# breadboard_power_supply_smd.net
KiCad netlist of a schematic drawn in EAGLE
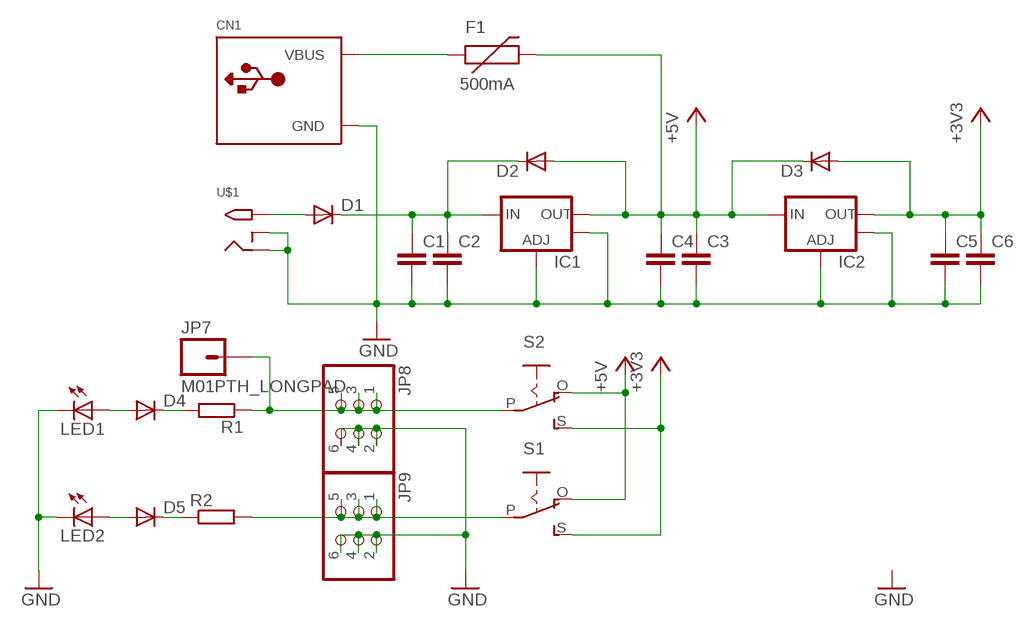
[diagram p0: schematic, sheet 1]

(export (version "E")
  (design (tool "Eeschema 10.0.6"))
  (components
    (comp (ref "C1")
      (value "C-EUC0805K")
      (footprint "eagle-import:C0805K")
      (libsource (lib "eagle-import") (part "C-EUC0805K"))
    )
    (comp (ref "C2")
      (value "C-EUC0805K")
      (footprint "eagle-import:C0805K")
      (libsource (lib "eagle-import") (part "C-EUC0805K"))
    )
    (comp (ref "C3")
      (value "C-EUC0805K")
      (footprint "eagle-import:C0805K")
      (libsource (lib "eagle-import") (part "C-EUC0805K"))
    )
    (comp (ref "C4")
      (value "C-EUC0805K")
      (footprint "eagle-import:C0805K")
      (libsource (lib "eagle-import") (part "C-EUC0805K"))
    )
    (comp (ref "C5")
      (value "C-EUC0805K")
      (footprint "eagle-import:C0805K")
      (libsource (lib "eagle-import") (part "C-EUC0805K"))
    )
    (comp (ref "C6")
      (value "C-EUC0805K")
      (footprint "eagle-import:C0805K")
      (libsource (lib "eagle-import") (part "C-EUC0805K"))
    )
    (comp (ref "CN1")
      (value "USBPWR-ONLY")
      (footprint "eagle-import:USB-MINIB-THM")
      (libsource (lib "eagle-import") (part "USBPWR-ONLY"))
    )
    (comp (ref "D1")
      (value "DIODE-MINIMELF")
      (footprint "eagle-import:MINIMELF")
      (libsource (lib "eagle-import") (part "DIODE-MINIMELF"))
    )
    (comp (ref "D2")
      (value "DIODE-MINIMELF")
      (footprint "eagle-import:MINIMELF")
      (libsource (lib "eagle-import") (part "DIODE-MINIMELF"))
    )
    (comp (ref "D3")
      (value "DIODE-MINIMELF")
      (footprint "eagle-import:MINIMELF")
      (libsource (lib "eagle-import") (part "DIODE-MINIMELF"))
    )
    (comp (ref "D4")
      (value "DIODE-MINIMELF")
      (footprint "eagle-import:MINIMELF")
      (libsource (lib "eagle-import") (part "DIODE-MINIMELF"))
    )
    (comp (ref "D5")
      (value "DIODE-MINIMELF")
      (footprint "eagle-import:MINIMELF")
      (libsource (lib "eagle-import") (part "DIODE-MINIMELF"))
    )
    (comp (ref "F1")
      (value "500mA")
      (footprint "eagle-import:0603")
      (libsource (lib "eagle-import") (part "PTC0603"))
    )
    (comp (ref "IC1")
      (value "V_REG_LM1117SOT223")
      (footprint "eagle-import:SOT223")
      (libsource (lib "eagle-import") (part "V_REG_LM1117SOT223"))
    )
    (comp (ref "IC2")
      (value "V_REG_LM1117SOT223")
      (footprint "eagle-import:SOT223")
      (libsource (lib "eagle-import") (part "V_REG_LM1117SOT223"))
    )
    (comp (ref "JP7")
      (value "M01PTH_LONGPAD")
      (footprint "eagle-import:1X01_LONGPAD")
      (libsource (lib "eagle-import") (part "M01PTH_LONGPAD"))
    )
    (comp (ref "JP8")
      (value "PINHD-2X3")
      (footprint "eagle-import:2X03")
      (libsource (lib "eagle-import") (part "PINHD-2X3"))
    )
    (comp (ref "JP9")
      (value "PINHD-2X3")
      (footprint "eagle-import:2X03")
      (libsource (lib "eagle-import") (part "PINHD-2X3"))
    )
    (comp (ref "LED1")
      (value "LEDCHIP-LED0805")
      (footprint "eagle-import:CHIP-LED0805")
      (libsource (lib "eagle-import") (part "LEDCHIP-LED0805"))
    )
    (comp (ref "LED2")
      (value "LEDCHIP-LED0805")
      (footprint "eagle-import:CHIP-LED0805")
      (libsource (lib "eagle-import") (part "LEDCHIP-LED0805"))
    )
    (comp (ref "R1")
      (value "R-EU_R0805")
      (footprint "eagle-import:R0805")
      (libsource (lib "eagle-import") (part "R-EU_R0805"))
    )
    (comp (ref "R2")
      (value "R-EU_R0805")
      (footprint "eagle-import:R0805")
      (libsource (lib "eagle-import") (part "R-EU_R0805"))
    )
    (comp (ref "S1")
      (value "EG1218S")
      (footprint "eagle-import:EG1218")
      (libsource (lib "eagle-import") (part "EG1218S"))
    )
    (comp (ref "S2")
      (value "EG1218S")
      (footprint "eagle-import:EG1218")
      (libsource (lib "eagle-import") (part "EG1218S"))
    )
    (comp (ref "U$1")
      (value "2.1MMJACKTHM")
      (footprint "eagle-import:PJ-102A")
      (libsource (lib "eagle-import") (part "2.1MMJACKTHM"))
    )
  )
  (nets
    (net (code "1") (name "+3V3") (class "Default")
      (node (ref "C5") (pin "1") (pinfunction "1_1") (pintype "passive"))
      (node (ref "C6") (pin "1") (pinfunction "1_1") (pintype "passive"))
      (node (ref "D3") (pin "A") (pinfunction "A_A") (pintype "passive"))
      (node (ref "IC2") (pin "2") (pinfunction "OUT_2") (pintype "output"))
      (node (ref "S1") (pin "S") (pinfunction "S_S") (pintype "passive"))
      (node (ref "S2") (pin "S") (pinfunction "S_S") (pintype "passive"))
    )
    (net (code "2") (name "+5V") (class "Default")
      (node (ref "C3") (pin "1") (pinfunction "1_1") (pintype "passive"))
      (node (ref "C4") (pin "1") (pinfunction "1_1") (pintype "passive"))
      (node (ref "D2") (pin "A") (pinfunction "A_A") (pintype "passive"))
      (node (ref "D3") (pin "C") (pinfunction "C_C") (pintype "passive"))
      (node (ref "F1") (pin "2") (pinfunction "2_2") (pintype "bidirectional"))
      (node (ref "IC1") (pin "2") (pinfunction "OUT_2") (pintype "output"))
      (node (ref "IC2") (pin "3") (pinfunction "IN_3") (pintype "input"))
      (node (ref "S1") (pin "O") (pinfunction "O_O") (pintype "passive"))
      (node (ref "S2") (pin "O") (pinfunction "O_O") (pintype "passive"))
    )
    (net (code "3") (name "GND") (class "Default")
      (node (ref "C1") (pin "2") (pinfunction "2_2") (pintype "passive"))
      (node (ref "C2") (pin "2") (pinfunction "2_2") (pintype "passive"))
      (node (ref "C3") (pin "2") (pinfunction "2_2") (pintype "passive"))
      (node (ref "C4") (pin "2") (pinfunction "2_2") (pintype "passive"))
      (node (ref "C5") (pin "2") (pinfunction "2_2") (pintype "passive"))
      (node (ref "C6") (pin "2") (pinfunction "2_2") (pintype "passive"))
      (node (ref "CN1") (pin "GND") (pinfunction "GND_GND") (pintype "power_in"))
      (node (ref "CN1") (pin "GND1") (pinfunction "GND_GND1") (pintype "power_in"))
      (node (ref "CN1") (pin "GND2") (pinfunction "GND_GND2") (pintype "power_in"))
      (node (ref "CN1") (pin "GND3") (pinfunction "GND_GND3") (pintype "power_in"))
      (node (ref "CN1") (pin "GND4") (pinfunction "GND_GND4") (pintype "power_in"))
      (node (ref "IC1") (pin "1") (pinfunction "ADJ_1") (pintype "input"))
      (node (ref "IC1") (pin "4") (pinfunction "OUT_4") (pintype "output"))
      (node (ref "IC2") (pin "1") (pinfunction "ADJ_1") (pintype "input"))
      (node (ref "IC2") (pin "4") (pinfunction "OUT_4") (pintype "output"))
      (node (ref "JP8") (pin "2") (pinfunction "2_2") (pintype "passive"))
      (node (ref "JP8") (pin "4") (pinfunction "4_4") (pintype "passive"))
      (node (ref "JP8") (pin "6") (pinfunction "6_6") (pintype "passive"))
      (node (ref "JP9") (pin "2") (pinfunction "2_2") (pintype "passive"))
      (node (ref "JP9") (pin "4") (pinfunction "4_4") (pintype "passive"))
      (node (ref "JP9") (pin "6") (pinfunction "6_6") (pintype "passive"))
      (node (ref "LED1") (pin "C") (pinfunction "C_C") (pintype "passive"))
      (node (ref "LED2") (pin "C") (pinfunction "C_C") (pintype "passive"))
      (node (ref "U$1") (pin "RING") (pinfunction "RING_RING") (pintype "bidirectional"))
      (node (ref "U$1") (pin "RING_SW") (pinfunction "RING_SW_RING_SW") (pintype "bidirectional"))
    )
    (net (code "4") (name "Net-(CN1-PadVBUS)") (class "Default")
      (node (ref "CN1") (pin "VBUS") (pinfunction "VBUS_VBUS") (pintype "power_in"))
      (node (ref "F1") (pin "1") (pinfunction "1_1") (pintype "bidirectional"))
    )
    (net (code "5") (name "Net-(D1-PadA)") (class "Default")
      (node (ref "D1") (pin "A") (pinfunction "A_A") (pintype "passive"))
      (node (ref "U$1") (pin "TIP") (pinfunction "TIP_TIP") (pintype "bidirectional"))
    )
    (net (code "6") (name "Net-(D4-PadA)") (class "Default")
      (node (ref "D4") (pin "A") (pinfunction "A_A") (pintype "passive"))
      (node (ref "LED1") (pin "A") (pinfunction "A_A") (pintype "passive"))
    )
    (net (code "7") (name "Net-(D4-PadC)") (class "Default")
      (node (ref "D4") (pin "C") (pinfunction "C_C") (pintype "passive"))
      (node (ref "R1") (pin "2") (pinfunction "2_2") (pintype "passive"))
    )
    (net (code "8") (name "Net-(D5-PadA)") (class "Default")
      (node (ref "D5") (pin "A") (pinfunction "A_A") (pintype "passive"))
      (node (ref "LED2") (pin "A") (pinfunction "A_A") (pintype "passive"))
    )
    (net (code "9") (name "Net-(D5-PadC)") (class "Default")
      (node (ref "D5") (pin "C") (pinfunction "C_C") (pintype "passive"))
      (node (ref "R2") (pin "1") (pinfunction "1_1") (pintype "passive"))
    )
    (net (code "10") (name "Net-(IC1-IN)") (class "Default")
      (node (ref "C1") (pin "1") (pinfunction "1_1") (pintype "passive"))
      (node (ref "C2") (pin "1") (pinfunction "1_1") (pintype "passive"))
      (node (ref "D1") (pin "C") (pinfunction "C_C") (pintype "passive"))
      (node (ref "D2") (pin "C") (pinfunction "C_C") (pintype "passive"))
      (node (ref "IC1") (pin "3") (pinfunction "IN_3") (pintype "input"))
    )
    (net (code "11") (name "Net-(JP7-Pad1)") (class "Default")
      (node (ref "JP7") (pin "1") (pinfunction "1_1") (pintype "passive"))
      (node (ref "JP8") (pin "1") (pinfunction "1_1") (pintype "passive"))
      (node (ref "JP8") (pin "3") (pinfunction "3_3") (pintype "passive"))
      (node (ref "JP8") (pin "5") (pinfunction "5_5") (pintype "passive"))
      (node (ref "R1") (pin "1") (pinfunction "1_1") (pintype "passive"))
      (node (ref "S2") (pin "P") (pinfunction "P_P") (pintype "passive"))
    )
    (net (code "12") (name "Net-(JP9-Pad1)") (class "Default")
      (node (ref "JP9") (pin "1") (pinfunction "1_1") (pintype "passive"))
      (node (ref "JP9") (pin "3") (pinfunction "3_3") (pintype "passive"))
      (node (ref "JP9") (pin "5") (pinfunction "5_5") (pintype "passive"))
      (node (ref "R2") (pin "2") (pinfunction "2_2") (pintype "passive"))
      (node (ref "S1") (pin "P") (pinfunction "P_P") (pintype "passive"))
    )
  )
)
